# Dice-v1_1.net
KiCad netlist of a schematic drawn in EAGLE
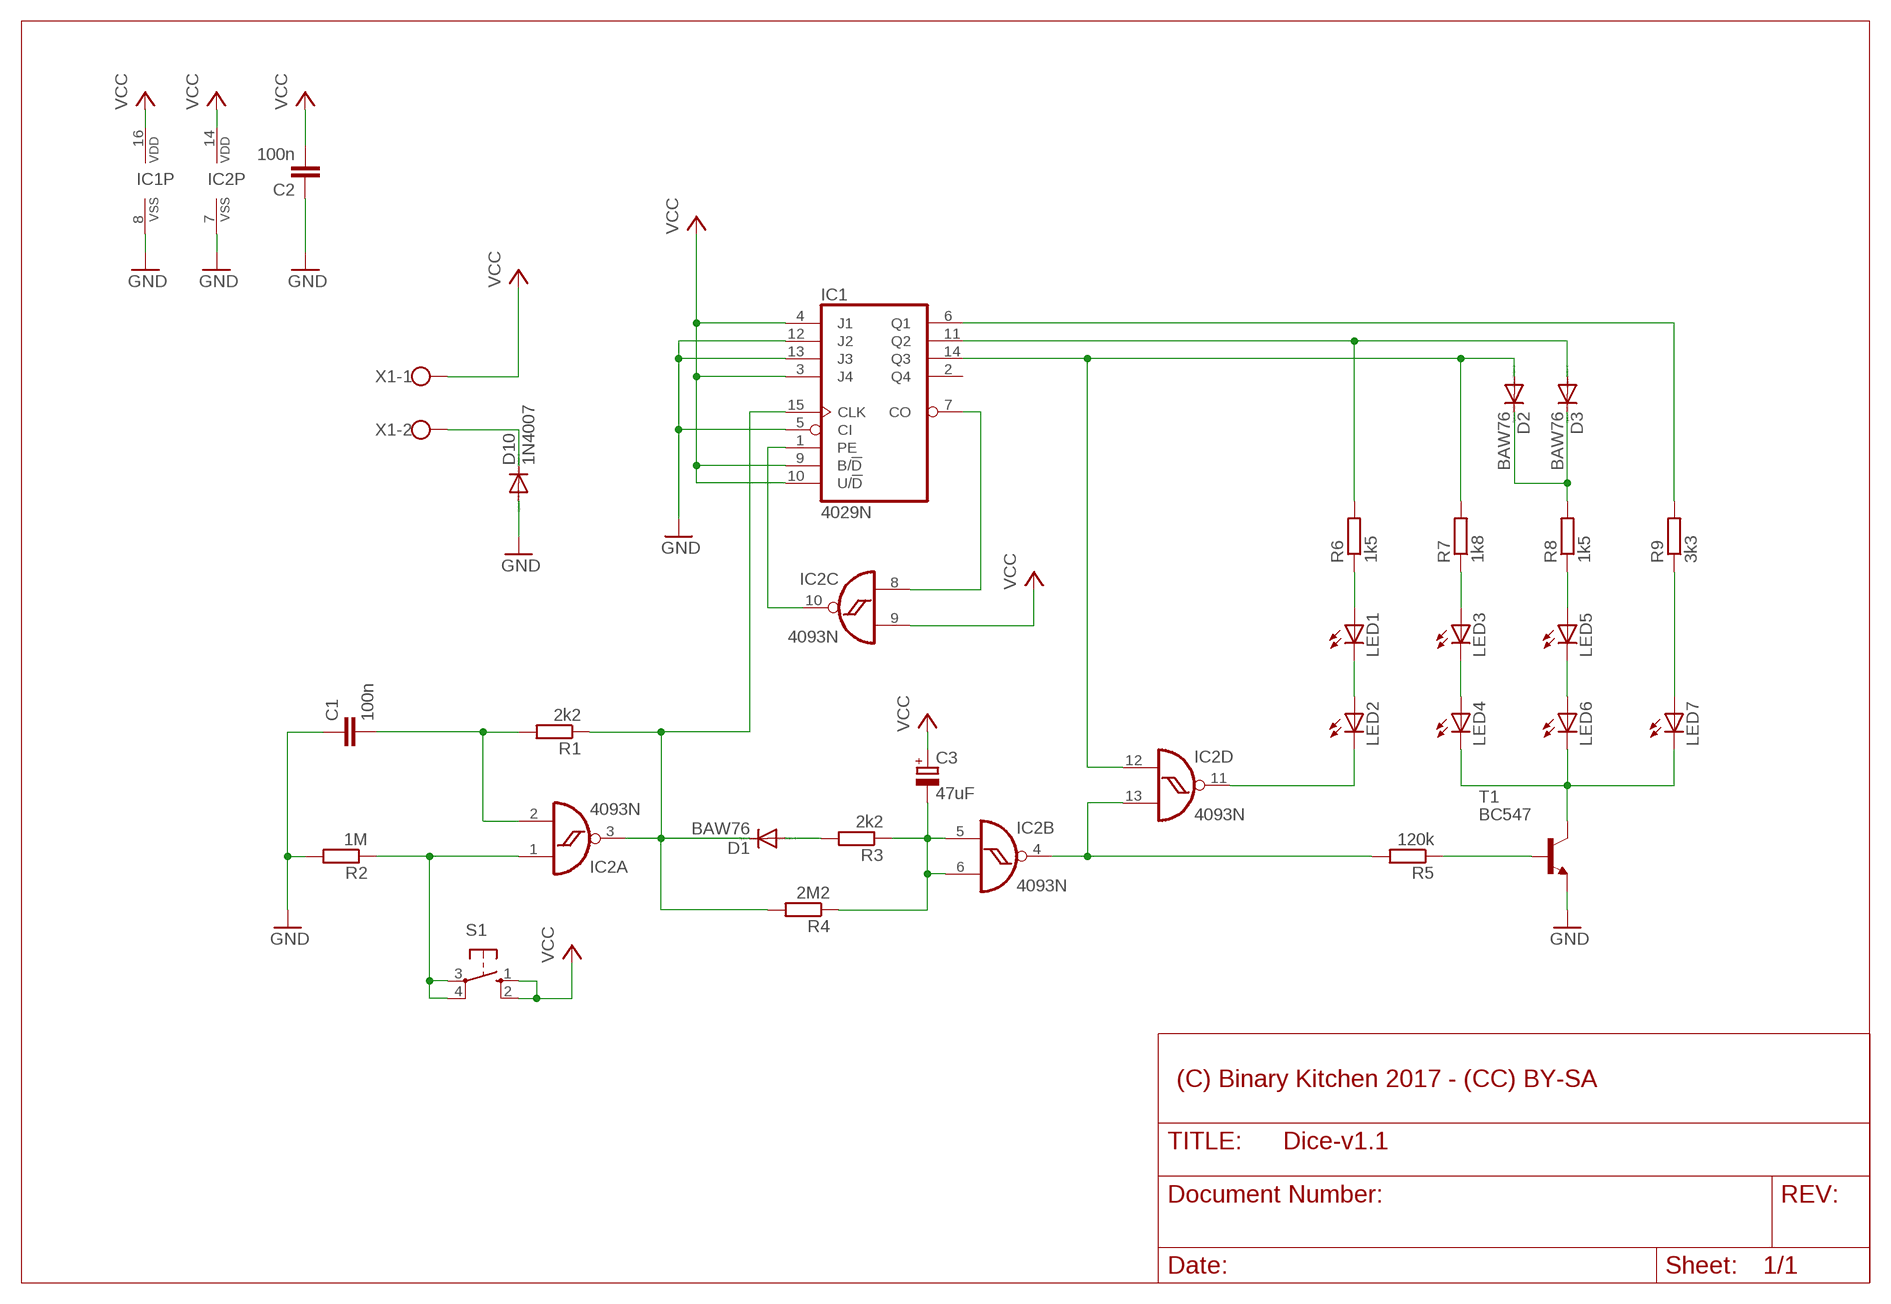
[diagram p0: schematic, sheet 1]

(export (version "E")
  (design (tool "Eeschema 10.0.6"))
  (components
    (comp (ref "C1")
      (value "100n")
      (footprint "eagle-import:C050-025X075")
      (libsource (lib "eagle-import") (part "C-EU050-025X075"))
    )
    (comp (ref "C2")
      (value "100n")
      (footprint "eagle-import:C050-025X075")
      (libsource (lib "eagle-import") (part "C-EU050-025X075"))
    )
    (comp (ref "C3")
      (value "47uF")
      (footprint "eagle-import:E2-5")
      (libsource (lib "eagle-import") (part "CPOL-EUE2-5"))
    )
    (comp (ref "D1")
      (value "BAW76")
      (footprint "eagle-import:DO35-10")
      (libsource (lib "eagle-import") (part "BAW75"))
    )
    (comp (ref "D2")
      (value "BAW76")
      (footprint "eagle-import:DO35-10")
      (libsource (lib "eagle-import") (part "BAW75"))
    )
    (comp (ref "D3")
      (value "BAW76")
      (footprint "eagle-import:DO35-10")
      (libsource (lib "eagle-import") (part "BAW75"))
    )
    (comp (ref "D10")
      (value "1N4007")
      (footprint "eagle-import:DO41-10")
      (libsource (lib "eagle-import") (part "1N4004"))
    )
    (comp (ref "IC1")
      (value "4029N")
      (footprint "eagle-import:DIL16")
      (libsource (lib "eagle-import") (part "4029N"))
    )
    (comp (ref "IC2")
      (value "4093N")
      (footprint "eagle-import:DIL14")
      (libsource (lib "eagle-import") (part "4093N"))
    )
    (comp (ref "LED1")
      (value "LED5MM")
      (footprint "eagle-import:LED5MM")
      (libsource (lib "eagle-import") (part "LED5MM"))
    )
    (comp (ref "LED2")
      (value "LED5MM")
      (footprint "eagle-import:LED5MM")
      (libsource (lib "eagle-import") (part "LED5MM"))
    )
    (comp (ref "LED3")
      (value "LED5MM")
      (footprint "eagle-import:LED5MM")
      (libsource (lib "eagle-import") (part "LED5MM"))
    )
    (comp (ref "LED4")
      (value "LED5MM")
      (footprint "eagle-import:LED5MM")
      (libsource (lib "eagle-import") (part "LED5MM"))
    )
    (comp (ref "LED5")
      (value "LED5MM")
      (footprint "eagle-import:LED5MM")
      (libsource (lib "eagle-import") (part "LED5MM"))
    )
    (comp (ref "LED6")
      (value "LED5MM")
      (footprint "eagle-import:LED5MM")
      (libsource (lib "eagle-import") (part "LED5MM"))
    )
    (comp (ref "LED7")
      (value "LED5MM")
      (footprint "eagle-import:LED5MM")
      (libsource (lib "eagle-import") (part "LED5MM"))
    )
    (comp (ref "R1")
      (value "2k2")
      (footprint "eagle-import:0207_7")
      (libsource (lib "eagle-import") (part "R-EU_0207/7"))
    )
    (comp (ref "R2")
      (value "1M")
      (footprint "eagle-import:0207_7")
      (libsource (lib "eagle-import") (part "R-EU_0207/7"))
    )
    (comp (ref "R3")
      (value "2k2")
      (footprint "eagle-import:0207_7")
      (libsource (lib "eagle-import") (part "R-EU_0207/7"))
    )
    (comp (ref "R4")
      (value "2M2")
      (footprint "eagle-import:0207_7")
      (libsource (lib "eagle-import") (part "R-EU_0207/7"))
    )
    (comp (ref "R5")
      (value "120k")
      (footprint "eagle-import:0207_7")
      (libsource (lib "eagle-import") (part "R-EU_0207/7"))
    )
    (comp (ref "R6")
      (value "1k5")
      (footprint "eagle-import:0207_7")
      (libsource (lib "eagle-import") (part "R-EU_0207/7"))
    )
    (comp (ref "R7")
      (value "1k8")
      (footprint "eagle-import:0207_7")
      (libsource (lib "eagle-import") (part "R-EU_0207/7"))
    )
    (comp (ref "R8")
      (value "1k5")
      (footprint "eagle-import:0207_7")
      (libsource (lib "eagle-import") (part "R-EU_0207/7"))
    )
    (comp (ref "R9")
      (value "3k3")
      (footprint "eagle-import:0207_7")
      (libsource (lib "eagle-import") (part "R-EU_0207/7"))
    )
    (comp (ref "S1")
      (value "10-XX")
      (footprint "eagle-import:B3F-10XX")
      (fields (field (name "MPN") "B3F-1000"))
      (libsource (lib "eagle-import") (part "10-XX"))
    )
    (comp (ref "T1")
      (value "BC547")
      (footprint "eagle-import:TO92")
      (libsource (lib "eagle-import") (part "BC547"))
    )
    (comp (ref "X1")
      (value "W237-102")
      (footprint "eagle-import:W237-102")
      (fields (field (name "MPN") "237-102"))
      (libsource (lib "eagle-import") (part "W237-102"))
    )
  )
  (nets
    (net (code "1") (name "GND") (class "Default")
      (node (ref "C1") (pin "1") (pinfunction "1_1") (pintype "passive"))
      (node (ref "C2") (pin "1") (pinfunction "1_1") (pintype "passive"))
      (node (ref "D10") (pin "A") (pinfunction "A_A") (pintype "passive"))
      (node (ref "IC1") (pin "12") (pinfunction "J2_12") (pintype "input"))
      (node (ref "IC1") (pin "13") (pinfunction "J3_13") (pintype "input"))
      (node (ref "IC1") (pin "5") (pinfunction "CI_5") (pintype "input"))
      (node (ref "IC1") (pin "8") (pinfunction "VSS_8") (pintype "power_in"))
      (node (ref "IC2") (pin "7") (pinfunction "VSS_7") (pintype "power_in"))
      (node (ref "R2") (pin "2") (pinfunction "2_2") (pintype "passive"))
      (node (ref "T1") (pin "1") (pinfunction "E_1") (pintype "passive"))
    )
    (net (code "2") (name "Net-(D1-PadA)") (class "Default")
      (node (ref "D1") (pin "A") (pinfunction "A_A") (pintype "passive"))
      (node (ref "R3") (pin "2") (pinfunction "2_2") (pintype "passive"))
    )
    (net (code "3") (name "Net-(D2-PadC)") (class "Default")
      (node (ref "D2") (pin "C") (pinfunction "C_C") (pintype "passive"))
      (node (ref "D3") (pin "C") (pinfunction "C_C") (pintype "passive"))
      (node (ref "R8") (pin "2") (pinfunction "2_2") (pintype "passive"))
    )
    (net (code "4") (name "Net-(IC1A-CLK)") (class "Default")
      (node (ref "D1") (pin "C") (pinfunction "C_C") (pintype "passive"))
      (node (ref "IC1") (pin "15") (pinfunction "CLK_15") (pintype "input"))
      (node (ref "IC2") (pin "3") (pinfunction "O_3") (pintype "output"))
      (node (ref "R1") (pin "1") (pinfunction "1_1") (pintype "passive"))
      (node (ref "R4") (pin "2") (pinfunction "2_2") (pintype "passive"))
    )
    (net (code "5") (name "Net-(IC1A-CO)") (class "Default")
      (node (ref "IC1") (pin "7") (pinfunction "CO_7") (pintype "output"))
      (node (ref "IC2") (pin "8") (pinfunction "I0_8") (pintype "input"))
    )
    (net (code "6") (name "Net-(IC1A-PE)") (class "Default")
      (node (ref "IC1") (pin "1") (pinfunction "PE_1") (pintype "input"))
      (node (ref "IC2") (pin "10") (pinfunction "O_10") (pintype "output"))
    )
    (net (code "7") (name "Net-(IC1A-Q1)") (class "Default")
      (node (ref "IC1") (pin "6") (pinfunction "Q1_6") (pintype "output"))
      (node (ref "R9") (pin "2") (pinfunction "2_2") (pintype "passive"))
    )
    (net (code "8") (name "Net-(IC1A-Q2)") (class "Default")
      (node (ref "D3") (pin "A") (pinfunction "A_A") (pintype "passive"))
      (node (ref "IC1") (pin "11") (pinfunction "Q2_11") (pintype "output"))
      (node (ref "R6") (pin "2") (pinfunction "2_2") (pintype "passive"))
    )
    (net (code "9") (name "Net-(IC1A-Q3)") (class "Default")
      (node (ref "D2") (pin "A") (pinfunction "A_A") (pintype "passive"))
      (node (ref "IC1") (pin "14") (pinfunction "Q3_14") (pintype "output"))
      (node (ref "IC2") (pin "12") (pinfunction "I0_12") (pintype "input"))
      (node (ref "R7") (pin "2") (pinfunction "2_2") (pintype "passive"))
    )
    (net (code "10") (name "Net-(IC2A-I0)") (class "Default")
      (node (ref "IC2") (pin "1") (pinfunction "I0_1") (pintype "input"))
      (node (ref "R2") (pin "1") (pinfunction "1_1") (pintype "passive"))
      (node (ref "S1") (pin "3") (pinfunction "P_3") (pintype "passive"))
      (node (ref "S1") (pin "4") (pinfunction "P1_4") (pintype "passive"))
    )
    (net (code "11") (name "Net-(IC2A-I1)") (class "Default")
      (node (ref "C1") (pin "2") (pinfunction "2_2") (pintype "passive"))
      (node (ref "IC2") (pin "2") (pinfunction "I1_2") (pintype "input"))
      (node (ref "R1") (pin "2") (pinfunction "2_2") (pintype "passive"))
    )
    (net (code "12") (name "Net-(IC2B-I0)") (class "Default")
      (node (ref "C3") (pin "-") (pinfunction "-_-") (pintype "passive"))
      (node (ref "IC2") (pin "5") (pinfunction "I0_5") (pintype "input"))
      (node (ref "IC2") (pin "6") (pinfunction "I1_6") (pintype "input"))
      (node (ref "R3") (pin "1") (pinfunction "1_1") (pintype "passive"))
      (node (ref "R4") (pin "1") (pinfunction "1_1") (pintype "passive"))
    )
    (net (code "13") (name "Net-(IC2B-O)") (class "Default")
      (node (ref "IC2") (pin "13") (pinfunction "I1_13") (pintype "input"))
      (node (ref "IC2") (pin "4") (pinfunction "O_4") (pintype "output"))
      (node (ref "R5") (pin "2") (pinfunction "2_2") (pintype "passive"))
    )
    (net (code "14") (name "Net-(IC2D-O)") (class "Default")
      (node (ref "IC2") (pin "11") (pinfunction "O_11") (pintype "output"))
      (node (ref "LED2") (pin "K") (pinfunction "C_K") (pintype "passive"))
    )
    (net (code "15") (name "Net-(LED1-C)") (class "Default")
      (node (ref "LED1") (pin "K") (pinfunction "C_K") (pintype "passive"))
      (node (ref "LED2") (pin "A") (pinfunction "A_A") (pintype "passive"))
    )
    (net (code "16") (name "Net-(LED1-PadA)") (class "Default")
      (node (ref "LED1") (pin "A") (pinfunction "A_A") (pintype "passive"))
      (node (ref "R6") (pin "1") (pinfunction "1_1") (pintype "passive"))
    )
    (net (code "17") (name "Net-(LED3-C)") (class "Default")
      (node (ref "LED3") (pin "K") (pinfunction "C_K") (pintype "passive"))
      (node (ref "LED4") (pin "A") (pinfunction "A_A") (pintype "passive"))
    )
    (net (code "18") (name "Net-(LED3-PadA)") (class "Default")
      (node (ref "LED3") (pin "A") (pinfunction "A_A") (pintype "passive"))
      (node (ref "R7") (pin "1") (pinfunction "1_1") (pintype "passive"))
    )
    (net (code "19") (name "Net-(LED4-C)") (class "Default")
      (node (ref "LED4") (pin "K") (pinfunction "C_K") (pintype "passive"))
      (node (ref "LED6") (pin "K") (pinfunction "C_K") (pintype "passive"))
      (node (ref "LED7") (pin "K") (pinfunction "C_K") (pintype "passive"))
      (node (ref "T1") (pin "3") (pinfunction "C_3") (pintype "passive"))
    )
    (net (code "20") (name "Net-(LED5-C)") (class "Default")
      (node (ref "LED5") (pin "K") (pinfunction "C_K") (pintype "passive"))
      (node (ref "LED6") (pin "A") (pinfunction "A_A") (pintype "passive"))
    )
    (net (code "21") (name "Net-(LED5-PadA)") (class "Default")
      (node (ref "LED5") (pin "A") (pinfunction "A_A") (pintype "passive"))
      (node (ref "R8") (pin "1") (pinfunction "1_1") (pintype "passive"))
    )
    (net (code "22") (name "Net-(LED7-PadA)") (class "Default")
      (node (ref "LED7") (pin "A") (pinfunction "A_A") (pintype "passive"))
      (node (ref "R9") (pin "1") (pinfunction "1_1") (pintype "passive"))
    )
    (net (code "23") (name "Net-(T1-B)") (class "Default")
      (node (ref "R5") (pin "1") (pinfunction "1_1") (pintype "passive"))
      (node (ref "T1") (pin "2") (pinfunction "B_2") (pintype "passive"))
    )
    (net (code "24") (name "Net-(X1B-KL)") (class "Default")
      (node (ref "D10") (pin "C") (pinfunction "C_C") (pintype "passive"))
      (node (ref "X1") (pin "2") (pinfunction "KL_2") (pintype "passive"))
    )
    (net (code "25") (name "VCC") (class "Default")
      (node (ref "C2") (pin "2") (pinfunction "2_2") (pintype "passive"))
      (node (ref "C3") (pin "+") (pinfunction "+_+") (pintype "passive"))
      (node (ref "IC1") (pin "10") (pinfunction "U/~{D}_10") (pintype "input"))
      (node (ref "IC1") (pin "16") (pinfunction "VDD_16") (pintype "power_in"))
      (node (ref "IC1") (pin "3") (pinfunction "J4_3") (pintype "input"))
      (node (ref "IC1") (pin "4") (pinfunction "J1_4") (pintype "input"))
      (node (ref "IC1") (pin "9") (pinfunction "B/~{D}_9") (pintype "input"))
      (node (ref "IC2") (pin "14") (pinfunction "VDD_14") (pintype "power_in"))
      (node (ref "IC2") (pin "9") (pinfunction "I1_9") (pintype "input"))
      (node (ref "S1") (pin "1") (pinfunction "S_1") (pintype "passive"))
      (node (ref "S1") (pin "2") (pinfunction "S1_2") (pintype "passive"))
      (node (ref "X1") (pin "1") (pinfunction "KL_1") (pintype "passive"))
    )
    (net (code "26") (name "unconnected-(IC1A-Q4-Pad2)") (class "Default")
      (node (ref "IC1") (pin "2") (pinfunction "Q4_2") (pintype "output"))
    )
  )
)
